# pCloud_ESP9266.net
KiCad netlist of a schematic drawn in EAGLE
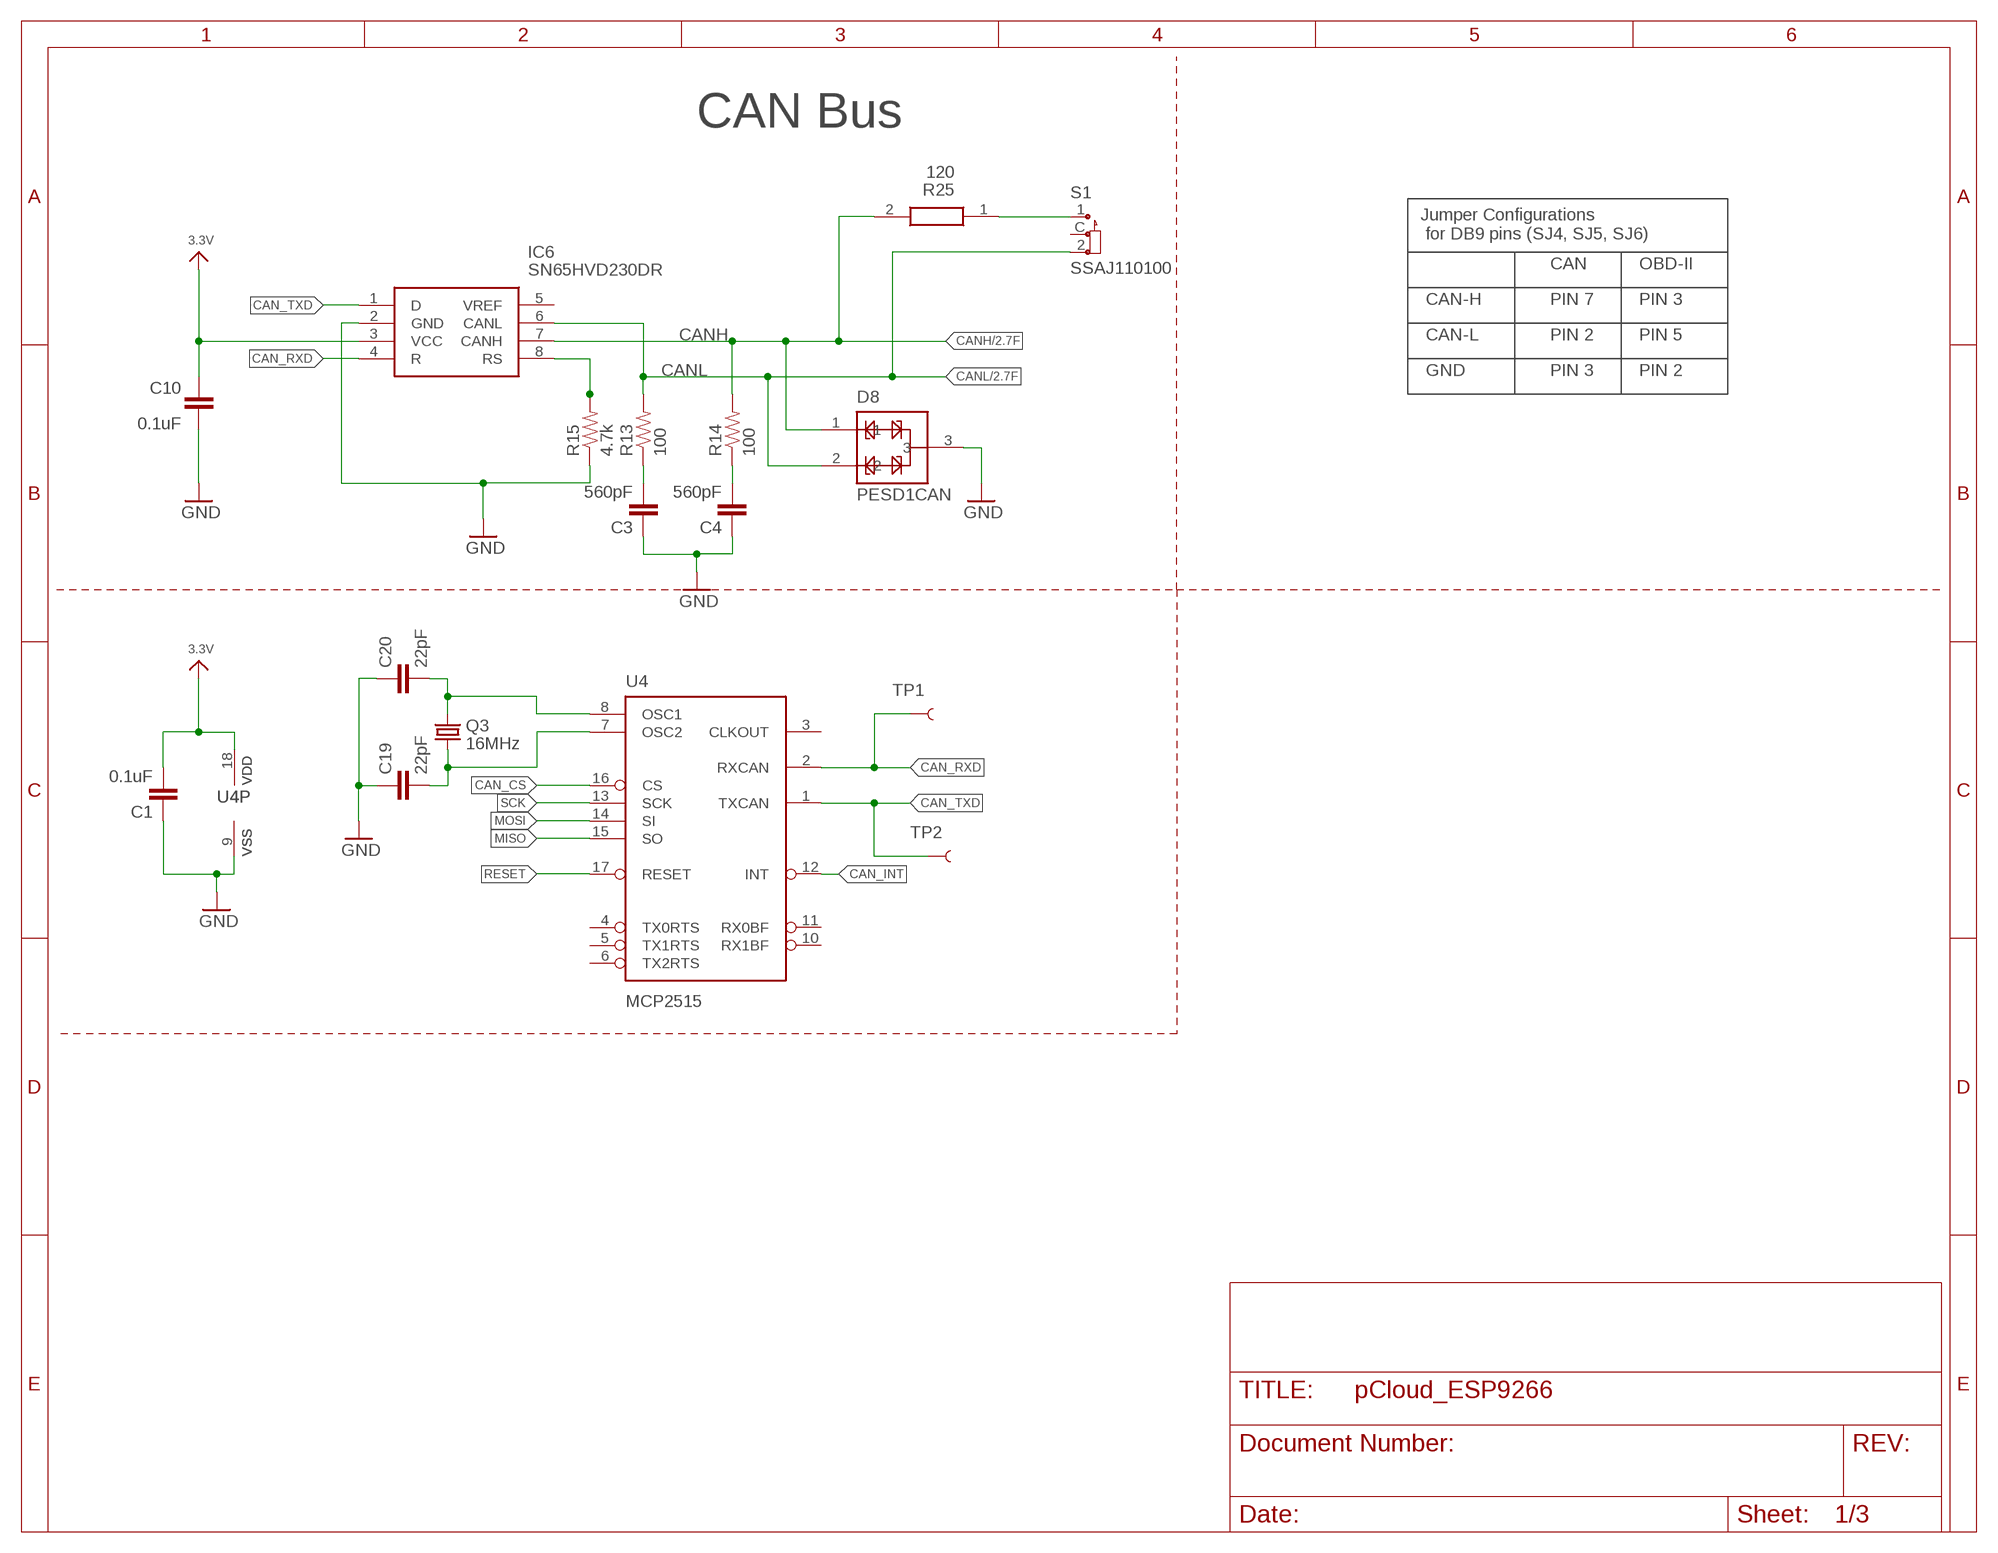
[diagram p0: schematic, sheet 1]
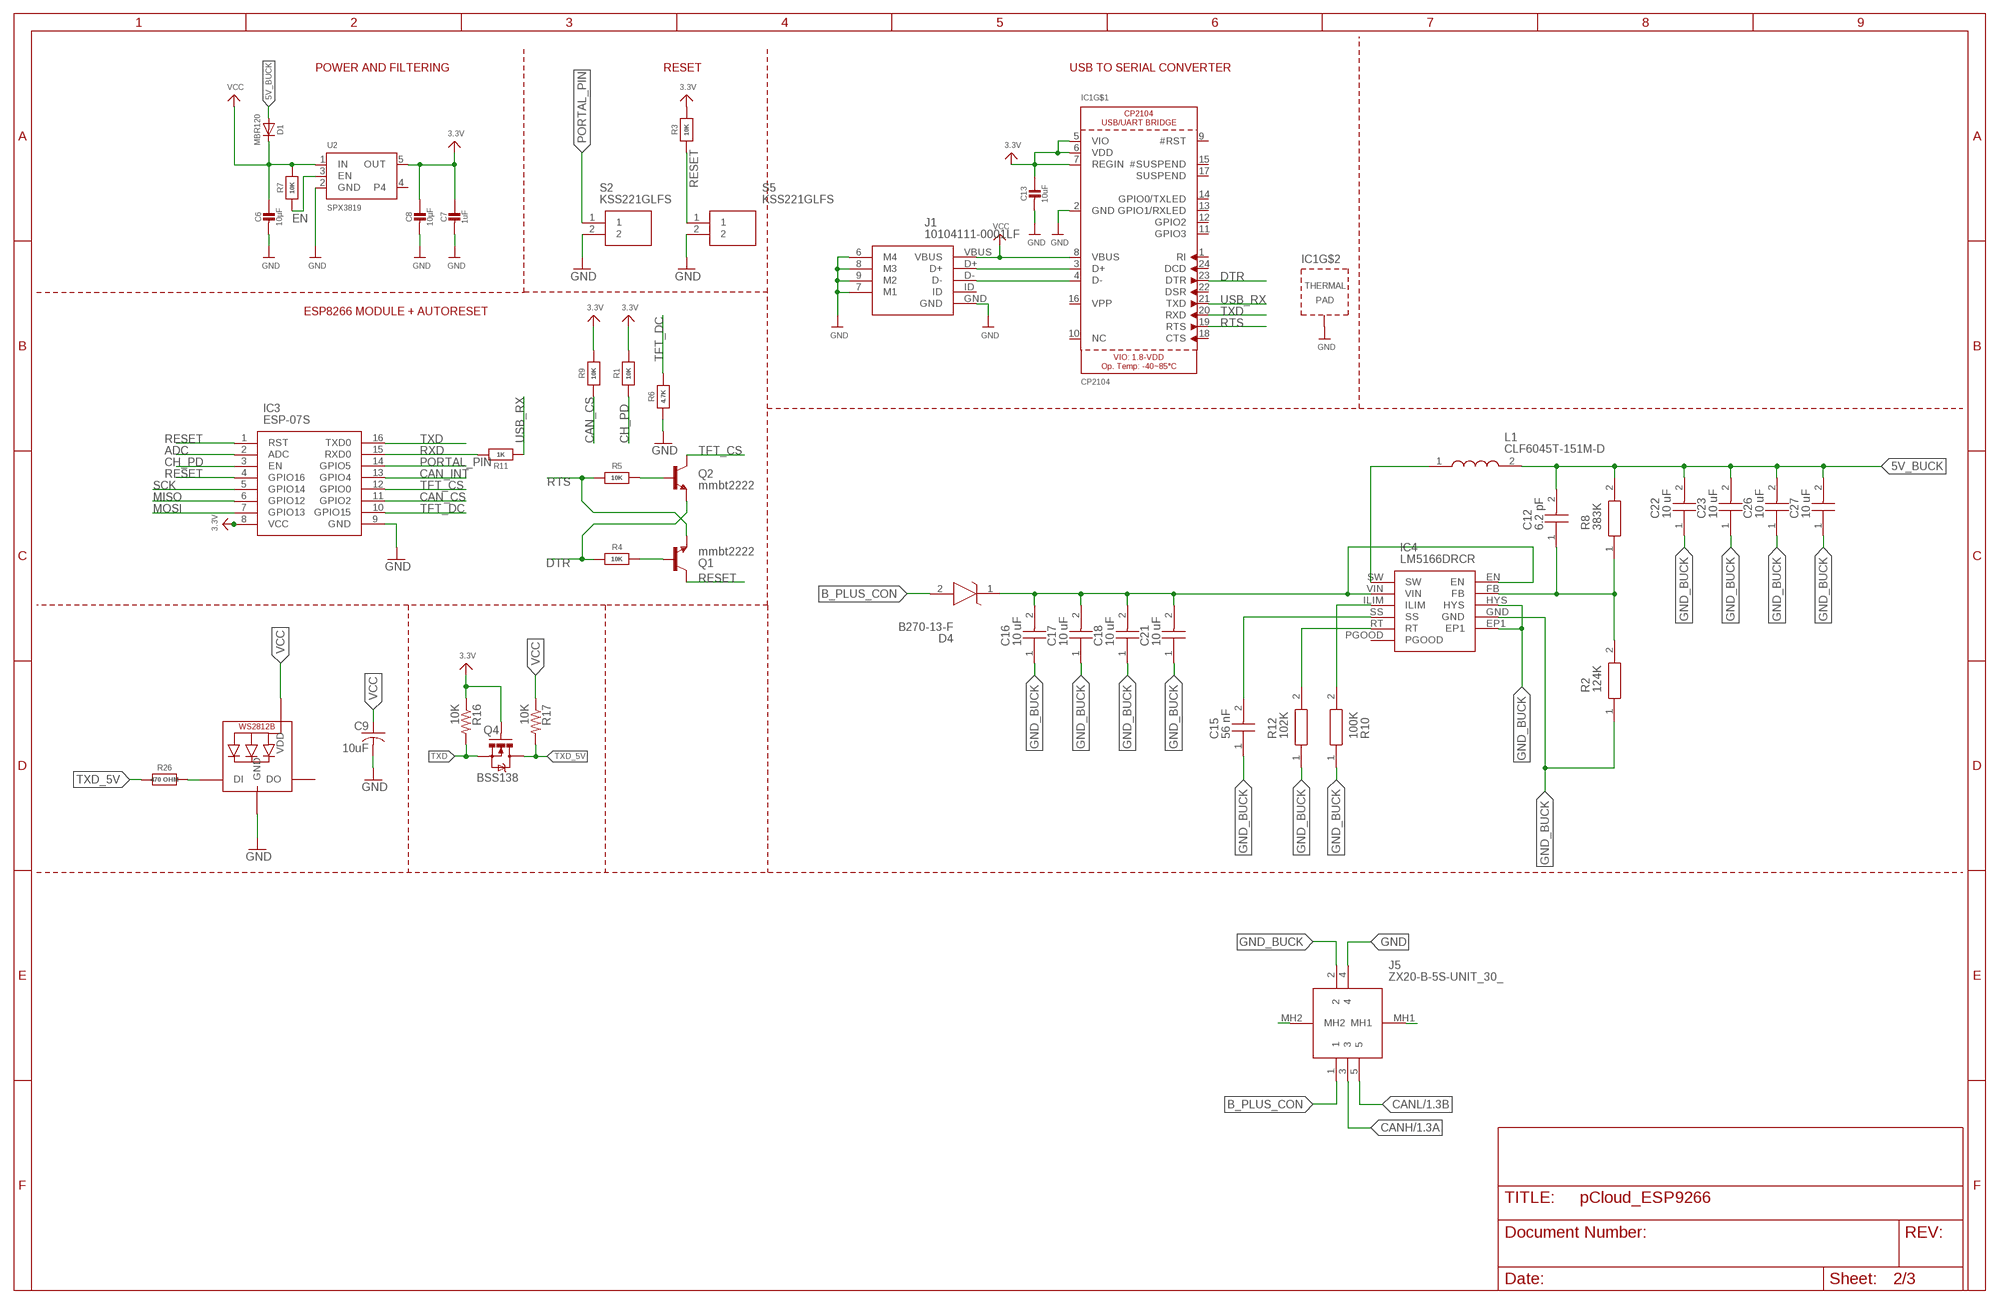
[diagram p1: schematic, sheet 2]
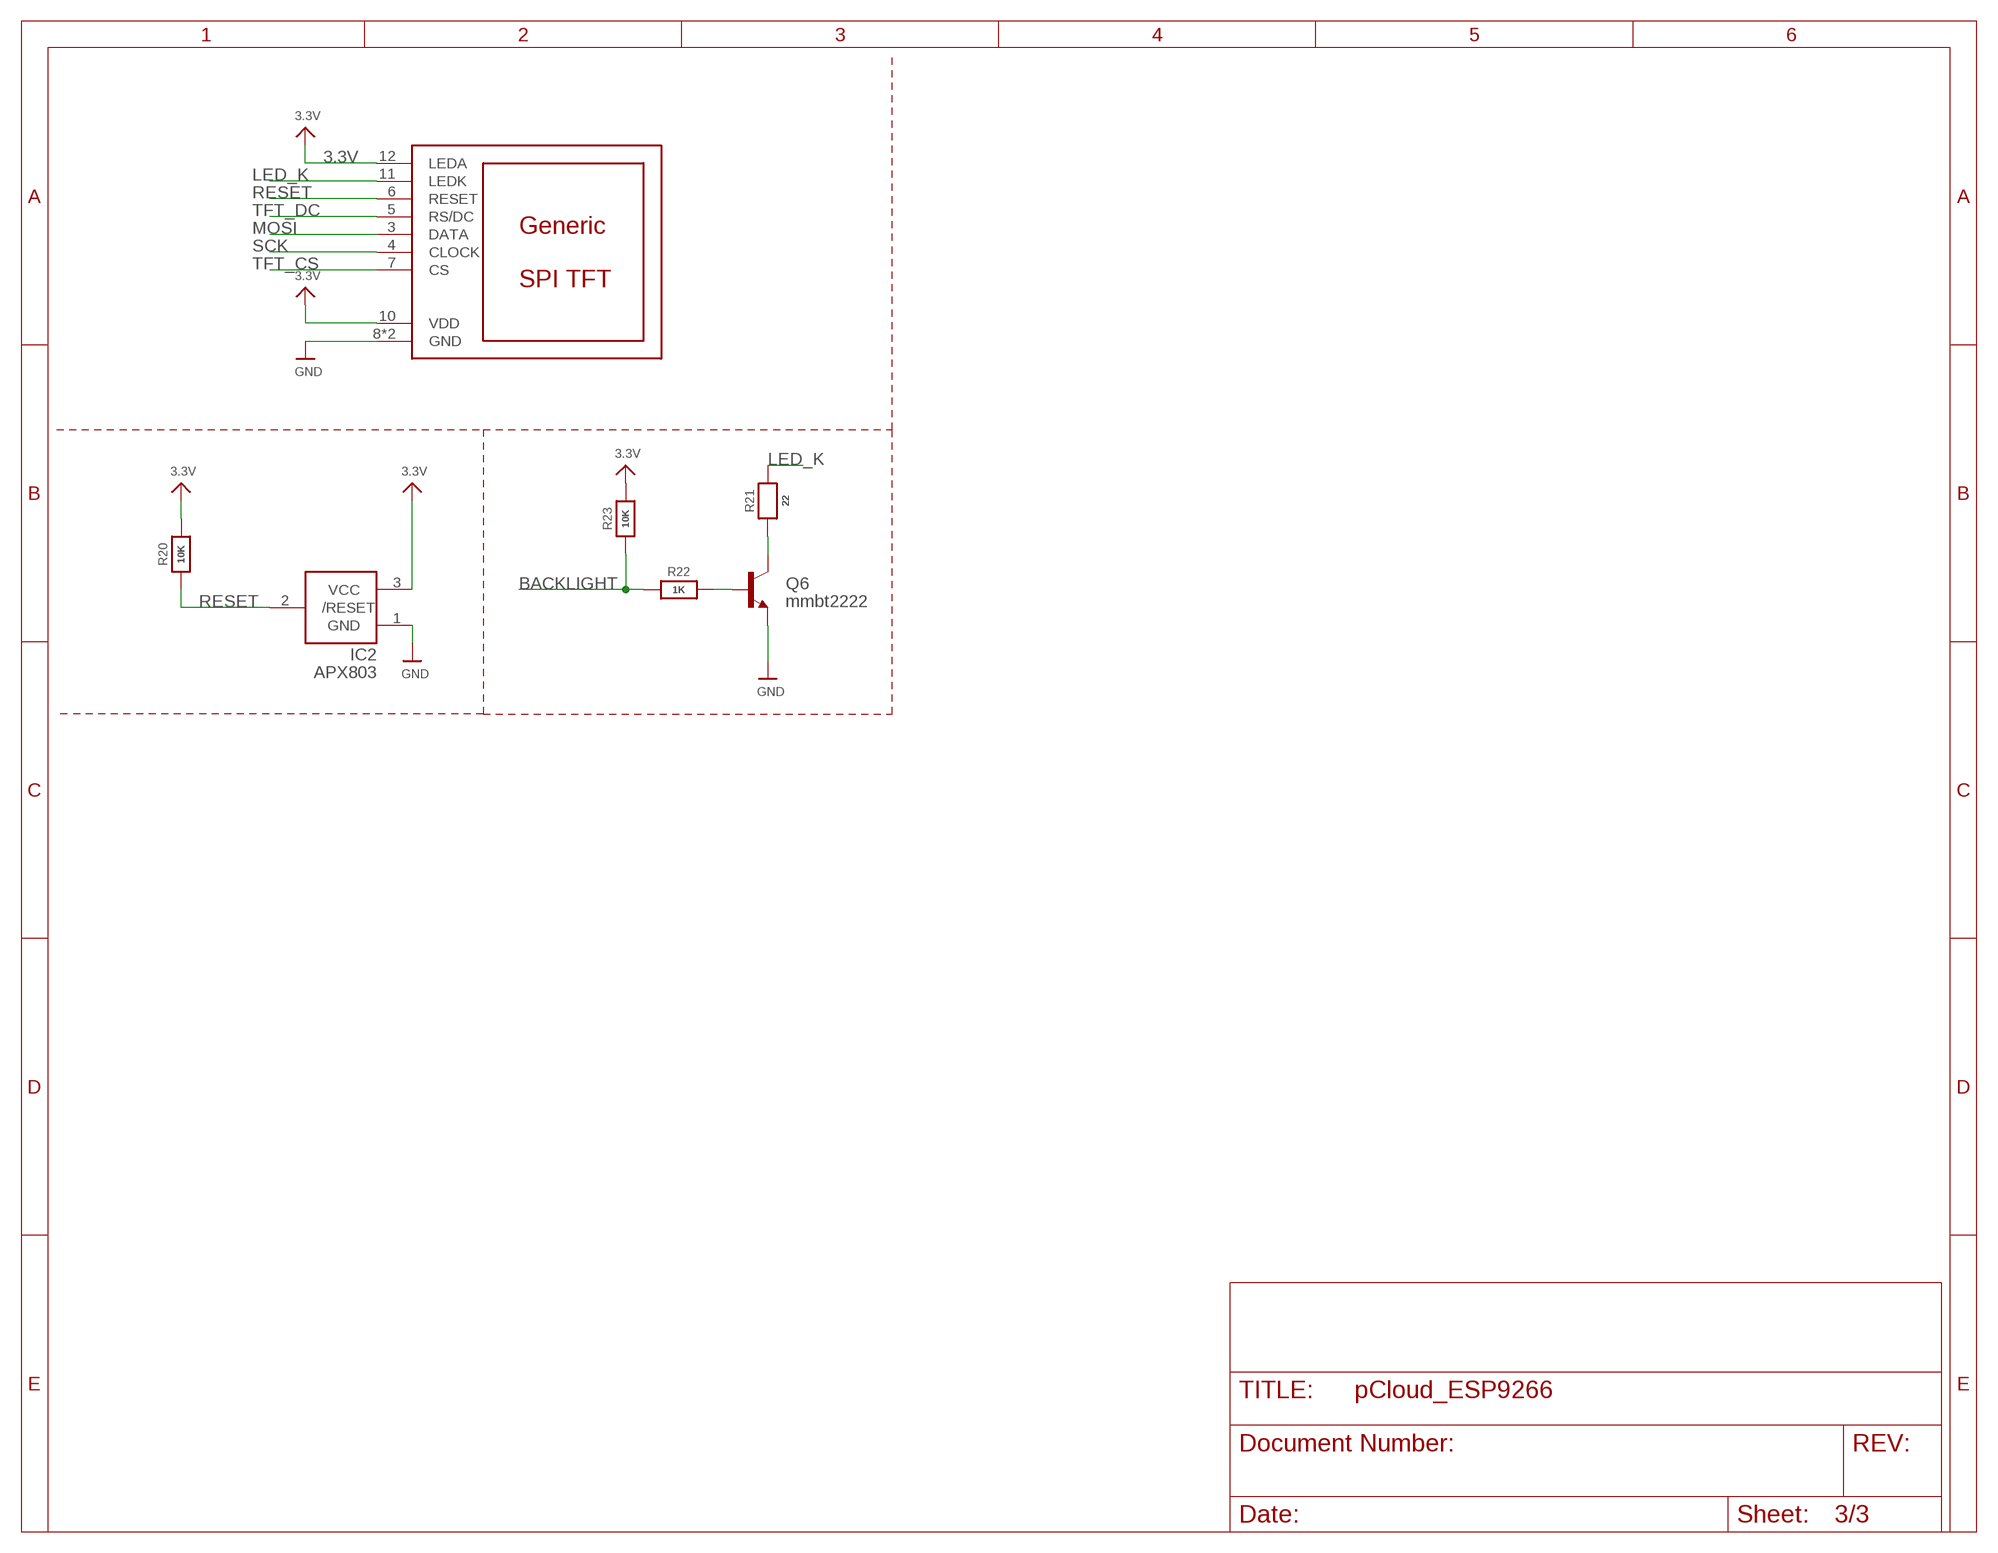
[diagram p2: schematic, sheet 3]

(export (version "E")
  (design (tool "Eeschema 10.0.6"))
  (components
    (comp (ref "C6")
      (value "10µF")
      (footprint "eagle-import:0805")
      (libsource (lib "eagle-import") (part "CAP_CERAMIC0805"))
    )
    (comp (ref "C7")
      (value "1uF")
      (footprint "eagle-import:0603")
      (libsource (lib "eagle-import") (part "CAP_CERAMIC0603"))
    )
    (comp (ref "C8")
      (value "10µF")
      (footprint "eagle-import:0805")
      (libsource (lib "eagle-import") (part "CAP_CERAMIC0805"))
    )
    (comp (ref "C9")
      (value "10uF")
      (footprint "eagle-import:C0805K")
      (libsource (lib "eagle-import") (part "C-USC0805K"))
    )
    (comp (ref "C12")
      (value "6.2 pF")
      (footprint "eagle-import:CAPC1005X55N")
      (fields
        (field (name "ARROW_PART_NUMBER") "GCM155R71C473KA37J")
        (field (name "MOUSER_PART_NUMBER") "81-GCM155R71C473KA7J")
      )
      (libsource (lib "eagle-import") (part "GCM155R71C473KA37J"))
    )
    (comp (ref "C13")
      (value "10uF")
      (footprint "eagle-import:0805")
      (libsource (lib "eagle-import") (part "CAP_CERAMIC0805"))
    )
    (comp (ref "C15")
      (value "56 nF")
      (footprint "eagle-import:CAPC1005X55N")
      (fields
        (field (name "ARROW_PART_NUMBER") "GCM155R71C473KA37J")
        (field (name "MOUSER_PART_NUMBER") "81-GCM155R71C473KA7J")
      )
      (libsource (lib "eagle-import") (part "GCM155R71C473KA37J"))
    )
    (comp (ref "C16")
      (value "10 uF")
      (footprint "eagle-import:CAPC3225X270N")
      (fields
        (field (name "ARROW_PART_NUMBER") "GRM32ER72A225KA35L")
        (field (name "MOUSER_PART_NUMBER") "81-GRM32ER72A225KA35")
      )
      (libsource (lib "eagle-import") (part "GRM32ER72A225KA35L"))
    )
    (comp (ref "C17")
      (value "10 uF")
      (footprint "eagle-import:CAPC3225X270N")
      (fields
        (field (name "ARROW_PART_NUMBER") "GRM32ER72A225KA35L")
        (field (name "MOUSER_PART_NUMBER") "81-GRM32ER72A225KA35")
      )
      (libsource (lib "eagle-import") (part "GRM32ER72A225KA35L"))
    )
    (comp (ref "C18")
      (value "10 uF")
      (footprint "eagle-import:CAPC3225X270N")
      (fields
        (field (name "ARROW_PART_NUMBER") "GRM32ER72A225KA35L")
        (field (name "MOUSER_PART_NUMBER") "81-GRM32ER72A225KA35")
      )
      (libsource (lib "eagle-import") (part "GRM32ER72A225KA35L"))
    )
    (comp (ref "C21")
      (value "10 uF")
      (footprint "eagle-import:CAPC3225X270N")
      (fields
        (field (name "ARROW_PART_NUMBER") "GRM32ER72A225KA35L")
        (field (name "MOUSER_PART_NUMBER") "81-GRM32ER72A225KA35")
      )
      (libsource (lib "eagle-import") (part "GRM32ER72A225KA35L"))
    )
    (comp (ref "C22")
      (value "10 uF")
      (footprint "eagle-import:CAPC3225X270N")
      (fields
        (field (name "ARROW_PART_NUMBER") "GRM32ER72A225KA35L")
        (field (name "MOUSER_PART_NUMBER") "81-GRM32ER72A225KA35")
      )
      (libsource (lib "eagle-import") (part "GRM32ER72A225KA35L"))
    )
    (comp (ref "C23")
      (value "10 uF")
      (footprint "eagle-import:CAPC3225X270N")
      (fields
        (field (name "ARROW_PART_NUMBER") "GRM32ER72A225KA35L")
        (field (name "MOUSER_PART_NUMBER") "81-GRM32ER72A225KA35")
      )
      (libsource (lib "eagle-import") (part "GRM32ER72A225KA35L"))
    )
    (comp (ref "C26")
      (value "10 uF")
      (footprint "eagle-import:CAPC3225X270N")
      (fields
        (field (name "ARROW_PART_NUMBER") "GRM32ER72A225KA35L")
        (field (name "MOUSER_PART_NUMBER") "81-GRM32ER72A225KA35")
      )
      (libsource (lib "eagle-import") (part "GRM32ER72A225KA35L"))
    )
    (comp (ref "C27")
      (value "10 uF")
      (footprint "eagle-import:CAPC3225X270N")
      (fields
        (field (name "ARROW_PART_NUMBER") "GRM32ER72A225KA35L")
        (field (name "MOUSER_PART_NUMBER") "81-GRM32ER72A225KA35")
      )
      (libsource (lib "eagle-import") (part "GRM32ER72A225KA35L"))
    )
    (comp (ref "D1")
      (value "MBR120")
      (footprint "eagle-import:SOD-123")
      (libsource (lib "eagle-import") (part "DIODESOD-123"))
    )
    (comp (ref "D4")
      (value "B270-13-F")
      (footprint "eagle-import:DIOM5336X250N")
      (fields (field (name "ARROW_PART_NUMBER") "B170B-13-F"))
      (libsource (lib "eagle-import") (part "B270B-13-F"))
    )
    (comp (ref "IC1")
      (value "CP2104")
      (footprint "eagle-import:QFN24_4MM_SMSC")
      (libsource (lib "eagle-import") (part "CP2104"))
    )
    (comp (ref "IC3")
      (value "ESP-07S")
      (footprint "eagle-import:ESP07S")
      (fields (field (name "MOUSER_PART_NUMBER") "223-ESP-07S") (field (name "RS_PART_NUMBER") "1372785"))
      (libsource (lib "eagle-import") (part "ESP-07S"))
    )
    (comp (ref "IC4")
      (value "LM5166DRCR")
      (footprint "eagle-import:TPS74901DRCR")
      (fields (field (name "MOUSER_PART_NUMBER") "595-LM5166DRCR"))
      (libsource (lib "eagle-import") (part "LM5166DRCR"))
    )
    (comp (ref "J1")
      (value "10104111-0001LF")
      (footprint "eagle-import:101041110001LF")
      (fields (field (name "MOUSER_PART_NUMBER") "649-10104111-0001LF"))
      (libsource (lib "eagle-import") (part "10104111-0001LF"))
    )
    (comp (ref "J5")
      (value "ZX20-B-5S-UNIT_30_")
      (footprint "eagle-import:ZX20B5SUNIT30")
      (fields
        (field (name "ARROW_PART_NUMBER") "ZX20-B-5S-UNIT(30)")
        (field (name "MOUSER_PART_NUMBER") "798-ZX20-B-5S-UNIT30")
      )
      (libsource (lib "eagle-import") (part "ZX20-B-5S-UNIT_30_"))
    )
    (comp (ref "L1")
      (value "CLF6045T-151M-D")
      (footprint "eagle-import:CLF6045T151MD")
      (fields (field (name "MOUSER_PART_NUMBER") "810-CLF6045T-151M-D"))
      (libsource (lib "eagle-import") (part "CLF6045T-151M-D"))
    )
    (comp (ref "LED4")
      (value "WS2812B5050")
      (footprint "eagle-import:WS2812B")
      (libsource (lib "eagle-import") (part "WS2812B5050"))
    )
    (comp (ref "Q1")
      (value "mmbt2222")
      (footprint "eagle-import:SOT23-3")
      (libsource (lib "eagle-import") (part "TRANSISTOR_NPNSOT23-3"))
    )
    (comp (ref "Q2")
      (value "mmbt2222")
      (footprint "eagle-import:SOT23-3")
      (libsource (lib "eagle-import") (part "TRANSISTOR_NPNSOT23-3"))
    )
    (comp (ref "Q4")
      (value "BSS138")
      (footprint "eagle-import:SOT23-3")
      (libsource (lib "eagle-import") (part "MOSFET-NCHANNELSMD"))
    )
    (comp (ref "R1")
      (value "10K")
      (footprint "eagle-import:0603")
      (libsource (lib "eagle-import") (part "RESISTOR0603"))
    )
    (comp (ref "R2")
      (value "124K")
      (footprint "eagle-import:RESC1005X40N")
      (fields
        (field (name "ARROW_PART_NUMBER") "RC0402FR-07100KP")
        (field (name "MOUSER_PART_NUMBER") "603-RC0402FR-07100KP")
      )
      (libsource (lib "eagle-import") (part "RC0402FR-07100KP"))
    )
    (comp (ref "R3")
      (value "10K")
      (footprint "eagle-import:0603")
      (libsource (lib "eagle-import") (part "RESISTOR0603"))
    )
    (comp (ref "R4")
      (value "10K")
      (footprint "eagle-import:0603")
      (libsource (lib "eagle-import") (part "RESISTOR0603"))
    )
    (comp (ref "R5")
      (value "10K")
      (footprint "eagle-import:0603")
      (libsource (lib "eagle-import") (part "RESISTOR_0603MP"))
    )
    (comp (ref "R6")
      (value "4.7K")
      (footprint "eagle-import:0603")
      (libsource (lib "eagle-import") (part "RESISTOR0603"))
    )
    (comp (ref "R7")
      (value "10K")
      (footprint "eagle-import:0603")
      (libsource (lib "eagle-import") (part "RESISTOR0603"))
    )
    (comp (ref "R8")
      (value "383K")
      (footprint "eagle-import:RESC1005X40N")
      (fields
        (field (name "ARROW_PART_NUMBER") "RC0402FR-07100KP")
        (field (name "MOUSER_PART_NUMBER") "603-RC0402FR-07100KP")
      )
      (libsource (lib "eagle-import") (part "RC0402FR-07100KP"))
    )
    (comp (ref "R9")
      (value "10K")
      (footprint "eagle-import:0603")
      (libsource (lib "eagle-import") (part "RESISTOR0603"))
    )
    (comp (ref "R10")
      (value "100K")
      (footprint "eagle-import:RESC1005X40N")
      (fields
        (field (name "ARROW_PART_NUMBER") "RC0402FR-07100KP")
        (field (name "MOUSER_PART_NUMBER") "603-RC0402FR-07100KP")
      )
      (libsource (lib "eagle-import") (part "RC0402FR-07100KP"))
    )
    (comp (ref "R11")
      (value "1K")
      (footprint "eagle-import:0603")
      (libsource (lib "eagle-import") (part "RESISTOR_0603MP"))
    )
    (comp (ref "R12")
      (value "102K")
      (footprint "eagle-import:RESC1005X40N")
      (fields
        (field (name "ARROW_PART_NUMBER") "RC0402FR-07100KP")
        (field (name "MOUSER_PART_NUMBER") "603-RC0402FR-07100KP")
      )
      (libsource (lib "eagle-import") (part "RC0402FR-07100KP"))
    )
    (comp (ref "R16")
      (value "10K")
      (footprint "eagle-import:0603")
      (libsource (lib "eagle-import") (part "RESISTOR0603-RES"))
    )
    (comp (ref "R17")
      (value "10K")
      (footprint "eagle-import:0603")
      (libsource (lib "eagle-import") (part "RESISTOR0603-RES"))
    )
    (comp (ref "R26")
      (value "470 OHM")
      (footprint "eagle-import:_0805MP")
      (libsource (lib "eagle-import") (part "RESISTOR_0805MP"))
    )
    (comp (ref "S2")
      (value "KSS221GLFS")
      (footprint "eagle-import:KSS")
      (fields (field (name "MOUSER_PART_NUMBER") "611-KSS221GLFS"))
      (libsource (lib "eagle-import") (part "KSS221GLFS"))
    )
    (comp (ref "S5")
      (value "KSS221GLFS")
      (footprint "eagle-import:KSS")
      (fields (field (name "MOUSER_PART_NUMBER") "611-KSS221GLFS"))
      (libsource (lib "eagle-import") (part "KSS221GLFS"))
    )
    (comp (ref "U2")
      (value "SPX3819")
      (footprint "eagle-import:SOT23-5")
      (libsource (lib "eagle-import") (part "VREG_SOT23-5"))
    )
    (comp (ref "DISP1")
      (value "DISP_LCD_GENERIC_SPI_1.14IN_240X135_WRAPUNDER")
      (footprint "eagle-import:TFT_1.14IN_240X135_WRAPUNDER")
      (libsource (lib "eagle-import") (part "DISP_LCD_GENERIC_SPI_1.14IN_240X135_WRAPUNDER"))
    )
    (comp (ref "IC2")
      (value "APX803")
      (footprint "eagle-import:SOT23")
      (libsource (lib "eagle-import") (part "AXP083-SAG"))
    )
    (comp (ref "Q6")
      (value "mmbt2222")
      (footprint "eagle-import:SOT23-3")
      (libsource (lib "eagle-import") (part "TRANSISTOR_NPNSOT23-3"))
    )
    (comp (ref "R20")
      (value "10K")
      (footprint "eagle-import:0603")
      (libsource (lib "eagle-import") (part "RESISTOR0603"))
    )
    (comp (ref "R21")
      (value "22")
      (footprint "eagle-import:0603")
      (libsource (lib "eagle-import") (part "RESISTOR0603"))
    )
    (comp (ref "R22")
      (value "1K")
      (footprint "eagle-import:0603")
      (libsource (lib "eagle-import") (part "RESISTOR0603"))
    )
    (comp (ref "R23")
      (value "10K")
      (footprint "eagle-import:0603")
      (libsource (lib "eagle-import") (part "RESISTOR0603"))
    )
    (comp (ref "C1")
      (value "0.1uF")
      (footprint "eagle-import:0603")
      (libsource (lib "eagle-import") (part "0.1UF-0603-25V-(+80/-20%)"))
    )
    (comp (ref "C3")
      (value "560pF")
      (footprint "eagle-import:0603")
      (libsource (lib "eagle-import") (part "560PF-0603-50V-5%"))
    )
    (comp (ref "C4")
      (value "560pF")
      (footprint "eagle-import:0603")
      (libsource (lib "eagle-import") (part "560PF-0603-50V-5%"))
    )
    (comp (ref "C10")
      (value "0.1uF")
      (footprint "eagle-import:0603")
      (libsource (lib "eagle-import") (part "0.1UF-0603-25V-(+80/-20%)"))
    )
    (comp (ref "C19")
      (value "22pF")
      (footprint "eagle-import:0603")
      (libsource (lib "eagle-import") (part "22PF-0603-50V-5%"))
    )
    (comp (ref "C20")
      (value "22pF")
      (footprint "eagle-import:0603")
      (libsource (lib "eagle-import") (part "22PF-0603-50V-5%"))
    )
    (comp (ref "D8")
      (value "PESD1CAN")
      (footprint "eagle-import:SOT23-3")
      (libsource (lib "eagle-import") (part "PESD1CAN"))
    )
    (comp (ref "IC6")
      (value "SN65HVD230DR")
      (footprint "eagle-import:SOT127P600X175-8N")
      (fields (field (name "MOUSER_PART_NUMBER") "595-SN65HVD230DR"))
      (libsource (lib "eagle-import") (part "SN65HVD230DR"))
    )
    (comp (ref "Q3")
      (value "16MHz")
      (footprint "eagle-import:CRYSTAL-SMD-5X3")
      (libsource (lib "eagle-import") (part "CRYSTAL5X3"))
    )
    (comp (ref "R13")
      (value "100")
      (footprint "eagle-import:0603")
      (libsource (lib "eagle-import") (part "100OHM-0603-1/10W-1%"))
    )
    (comp (ref "R14")
      (value "100")
      (footprint "eagle-import:0603")
      (libsource (lib "eagle-import") (part "100OHM-0603-1/10W-1%"))
    )
    (comp (ref "R15")
      (value "4.7k")
      (footprint "eagle-import:0603")
      (libsource (lib "eagle-import") (part "4.7KOHM-0603-1/10W-1%"))
    )
    (comp (ref "R25")
      (value "120")
      (footprint "eagle-import:RESC1608X55N")
      (fields
        (field (name "ARROW_PART_NUMBER") "RC0603JR-7W120RL")
        (field (name "MOUSER_PART_NUMBER") "603-RC0603JR-7W120RL")
      )
      (libsource (lib "eagle-import") (part "RC0603JR-7W120RL"))
    )
    (comp (ref "S1")
      (value "SSAJ110100")
      (footprint "eagle-import:SW_SSAJ110100")
      (fields (field (name "MF") "ALPS"))
      (libsource (lib "eagle-import") (part "SSAJ110100"))
    )
    (comp (ref "TP1")
      (value "TEST-POINT3X5")
      (footprint "eagle-import:PAD.03X.05")
      (libsource (lib "eagle-import") (part "TEST-POINT3X5"))
    )
    (comp (ref "TP2")
      (value "TEST-POINT3X5")
      (footprint "eagle-import:PAD.03X.05")
      (libsource (lib "eagle-import") (part "TEST-POINT3X5"))
    )
    (comp (ref "U4")
      (value "MCP2515")
      (footprint "eagle-import:SO-18W")
      (libsource (lib "eagle-import") (part "MCP2510SO"))
    )
  )
  (nets
    (net (code "1") (name "3.3V") (class "Default")
      (node (ref "C1") (pin "2") (pinfunction "2_2") (pintype "passive"))
      (node (ref "C10") (pin "2") (pinfunction "2_2") (pintype "passive"))
      (node (ref "C13") (pin "1") (pinfunction "P$1_1") (pintype "passive"))
      (node (ref "C7") (pin "1") (pinfunction "P$1_1") (pintype "passive"))
      (node (ref "C8") (pin "1") (pinfunction "P$1_1") (pintype "passive"))
      (node (ref "DISP1") (pin "10") (pinfunction "VDD_10") (pintype "power_in"))
      (node (ref "DISP1") (pin "12") (pinfunction "LEDA_12") (pintype "input"))
      (node (ref "IC1") (pin "5") (pinfunction "VIO_5") (pintype "power_in"))
      (node (ref "IC1") (pin "6") (pinfunction "VDD_6") (pintype "power_in"))
      (node (ref "IC1") (pin "7") (pinfunction "REGIN_7") (pintype "power_in"))
      (node (ref "IC2") (pin "3") (pinfunction "VCC_3") (pintype "power_in"))
      (node (ref "IC3") (pin "8") (pinfunction "VCC_8") (pintype "bidirectional"))
      (node (ref "IC6") (pin "3") (pinfunction "VCC_3") (pintype "bidirectional"))
      (node (ref "Q4") (pin "1") (pinfunction "G_1") (pintype "passive"))
      (node (ref "R1") (pin "2") (pinfunction "2_2") (pintype "passive"))
      (node (ref "R16") (pin "1") (pinfunction "1_1") (pintype "passive"))
      (node (ref "R20") (pin "2") (pinfunction "2_2") (pintype "passive"))
      (node (ref "R23") (pin "2") (pinfunction "2_2") (pintype "passive"))
      (node (ref "R3") (pin "2") (pinfunction "2_2") (pintype "passive"))
      (node (ref "R9") (pin "2") (pinfunction "2_2") (pintype "passive"))
      (node (ref "U2") (pin "5") (pinfunction "OUT_5") (pintype "bidirectional"))
      (node (ref "U4") (pin "18") (pinfunction "VDD_18") (pintype "power_in"))
    )
    (net (code "2") (name "5V_BUCK") (class "Default")
      (node (ref "C12") (pin "2") (pinfunction "2_2") (pintype "bidirectional"))
      (node (ref "C22") (pin "2") (pinfunction "C2_2") (pintype "bidirectional"))
      (node (ref "C23") (pin "2") (pinfunction "C2_2") (pintype "bidirectional"))
      (node (ref "C26") (pin "2") (pinfunction "C2_2") (pintype "bidirectional"))
      (node (ref "C27") (pin "2") (pinfunction "C2_2") (pintype "bidirectional"))
      (node (ref "D1") (pin "A") (pinfunction "A_A") (pintype "passive"))
      (node (ref "L1") (pin "2") (pinfunction "2_2") (pintype "bidirectional"))
      (node (ref "R8") (pin "2") (pinfunction "2_2") (pintype "bidirectional"))
    )
    (net (code "3") (name "ADC") (class "Default")
      (node (ref "IC3") (pin "2") (pinfunction "ADC_2") (pintype "bidirectional"))
    )
    (net (code "4") (name "BACKLIGHT") (class "Default")
      (node (ref "R22") (pin "1") (pinfunction "1_1") (pintype "passive"))
      (node (ref "R23") (pin "1") (pinfunction "1_1") (pintype "passive"))
    )
    (net (code "5") (name "B_PLUS_CON") (class "Default")
      (node (ref "D4") (pin "2") (pinfunction "A_2") (pintype "bidirectional"))
      (node (ref "J5") (pin "1") (pinfunction "1_1") (pintype "bidirectional"))
    )
    (net (code "6") (name "CANH") (class "Default")
      (node (ref "D8") (pin "1") (pinfunction "1_1") (pintype "bidirectional"))
      (node (ref "IC6") (pin "7") (pinfunction "CANH_7") (pintype "bidirectional"))
      (node (ref "J5") (pin "3") (pinfunction "3_3") (pintype "bidirectional"))
      (node (ref "R14") (pin "2") (pinfunction "2_2") (pintype "passive"))
      (node (ref "R25") (pin "2") (pinfunction "2_2") (pintype "bidirectional"))
    )
    (net (code "7") (name "CANL") (class "Default")
      (node (ref "D8") (pin "2") (pinfunction "2_2") (pintype "bidirectional"))
      (node (ref "IC6") (pin "6") (pinfunction "CANL_6") (pintype "bidirectional"))
      (node (ref "J5") (pin "5") (pinfunction "5_5") (pintype "bidirectional"))
      (node (ref "R13") (pin "2") (pinfunction "2_2") (pintype "passive"))
      (node (ref "S1") (pin "2") (pinfunction "2_2") (pintype "passive"))
    )
    (net (code "8") (name "CAN_CS") (class "Default")
      (node (ref "IC3") (pin "11") (pinfunction "GPIO2_11") (pintype "bidirectional"))
      (node (ref "R9") (pin "1") (pinfunction "1_1") (pintype "passive"))
      (node (ref "U4") (pin "16") (pinfunction "CS_16") (pintype "input"))
    )
    (net (code "9") (name "CAN_INT") (class "Default")
      (node (ref "IC3") (pin "13") (pinfunction "GPIO4_13") (pintype "bidirectional"))
      (node (ref "U4") (pin "12") (pinfunction "INT_12") (pintype "output"))
    )
    (net (code "10") (name "CAN_RXD") (class "Default")
      (node (ref "IC6") (pin "4") (pinfunction "R_4") (pintype "bidirectional"))
      (node (ref "TP1") (pin "P$1") (pinfunction "1_P$1") (pintype "bidirectional"))
      (node (ref "U4") (pin "2") (pinfunction "RXCAN_2") (pintype "input"))
    )
    (net (code "11") (name "CAN_TXD") (class "Default")
      (node (ref "IC6") (pin "1") (pinfunction "D_1") (pintype "bidirectional"))
      (node (ref "TP2") (pin "P$1") (pinfunction "1_P$1") (pintype "bidirectional"))
      (node (ref "U4") (pin "1") (pinfunction "TXCAN_1") (pintype "output"))
    )
    (net (code "12") (name "CH_PD") (class "Default")
      (node (ref "IC3") (pin "3") (pinfunction "EN_3") (pintype "bidirectional"))
      (node (ref "R1") (pin "1") (pinfunction "1_1") (pintype "passive"))
    )
    (net (code "13") (name "DTR") (class "Default")
      (node (ref "IC1") (pin "23") (pinfunction "DTR_23") (pintype "output"))
      (node (ref "Q2") (pin "2") (pinfunction "E_2") (pintype "passive"))
      (node (ref "R4") (pin "1") (pinfunction "1_1") (pintype "passive"))
    )
    (net (code "14") (name "EN") (class "Default")
      (node (ref "R7") (pin "1") (pinfunction "1_1") (pintype "passive"))
      (node (ref "U2") (pin "3") (pinfunction "EN_3") (pintype "bidirectional"))
    )
    (net (code "15") (name "GND") (class "Default")
      (node (ref "C1") (pin "1") (pinfunction "1_1") (pintype "passive"))
      (node (ref "C10") (pin "1") (pinfunction "1_1") (pintype "passive"))
      (node (ref "C13") (pin "2") (pinfunction "P$2_2") (pintype "passive"))
      (node (ref "C19") (pin "1") (pinfunction "1_1") (pintype "passive"))
      (node (ref "C20") (pin "1") (pinfunction "1_1") (pintype "passive"))
      (node (ref "C3") (pin "1") (pinfunction "1_1") (pintype "passive"))
      (node (ref "C4") (pin "1") (pinfunction "1_1") (pintype "passive"))
      (node (ref "C6") (pin "2") (pinfunction "P$2_2") (pintype "passive"))
      (node (ref "C7") (pin "2") (pinfunction "P$2_2") (pintype "passive"))
      (node (ref "C8") (pin "2") (pinfunction "P$2_2") (pintype "passive"))
      (node (ref "C9") (pin "2") (pinfunction "2_2") (pintype "passive"))
      (node (ref "D8") (pin "3") (pinfunction "3_3") (pintype "bidirectional"))
      (node (ref "DISP1") (pin "13") (pinfunction "GND_13") (pintype "power_in"))
      (node (ref "DISP1") (pin "8") (pinfunction "GND_8") (pintype "power_in"))
      (node (ref "IC1") (pin "2") (pinfunction "GND_2") (pintype "power_in"))
      (node (ref "IC1") (pin "THERM") (pinfunction "TP_THERM") (pintype "power_in"))
      (node (ref "IC2") (pin "1") (pinfunction "GND_1") (pintype "power_in"))
      (node (ref "IC3") (pin "9") (pinfunction "GND_9") (pintype "bidirectional"))
      (node (ref "IC6") (pin "2") (pinfunction "GND_2") (pintype "bidirectional"))
      (node (ref "J1") (pin "6") (pinfunction "M4_6") (pintype "bidirectional"))
      (node (ref "J1") (pin "7") (pinfunction "M1_7") (pintype "bidirectional"))
      (node (ref "J1") (pin "8") (pinfunction "M3_8") (pintype "bidirectional"))
      (node (ref "J1") (pin "9") (pinfunction "M2_9") (pintype "bidirectional"))
      (node (ref "J1") (pin "GND") (pinfunction "GND_GND") (pintype "bidirectional"))
      (node (ref "J5") (pin "4") (pinfunction "4_4") (pintype "bidirectional"))
      (node (ref "LED4") (pin "3-GND") (pinfunction "GND_3-GND") (pintype "power_in"))
      (node (ref "Q6") (pin "2") (pinfunction "E_2") (pintype "passive"))
      (node (ref "R15") (pin "1") (pinfunction "1_1") (pintype "passive"))
      (node (ref "R6") (pin "1") (pinfunction "1_1") (pintype "passive"))
      (node (ref "S2") (pin "2") (pinfunction "2_2") (pintype "bidirectional"))
      (node (ref "S5") (pin "2") (pinfunction "2_2") (pintype "bidirectional"))
      (node (ref "U2") (pin "2") (pinfunction "GND_2") (pintype "bidirectional"))
      (node (ref "U4") (pin "9") (pinfunction "VSS_9") (pintype "power_in"))
    )
    (net (code "16") (name "GND_BUCK") (class "Default")
      (node (ref "C15") (pin "1") (pinfunction "1_1") (pintype "bidirectional"))
      (node (ref "C16") (pin "1") (pinfunction "C1_1") (pintype "bidirectional"))
      (node (ref "C17") (pin "1") (pinfunction "C1_1") (pintype "bidirectional"))
      (node (ref "C18") (pin "1") (pinfunction "C1_1") (pintype "bidirectional"))
      (node (ref "C21") (pin "1") (pinfunction "C1_1") (pintype "bidirectional"))
      (node (ref "C22") (pin "1") (pinfunction "C1_1") (pintype "bidirectional"))
      (node (ref "C23") (pin "1") (pinfunction "C1_1") (pintype "bidirectional"))
      (node (ref "C26") (pin "1") (pinfunction "C1_1") (pintype "bidirectional"))
      (node (ref "C27") (pin "1") (pinfunction "C1_1") (pintype "bidirectional"))
      (node (ref "IC4") (pin "EP1") (pinfunction "EP1_EP1") (pintype "bidirectional"))
      (node (ref "IC4") (pin "GND") (pinfunction "GND_GND") (pintype "bidirectional"))
      (node (ref "IC4") (pin "HYS") (pinfunction "HYS_HYS") (pintype "bidirectional"))
      (node (ref "J5") (pin "2") (pinfunction "2_2") (pintype "bidirectional"))
      (node (ref "R10") (pin "1") (pinfunction "1_1") (pintype "bidirectional"))
      (node (ref "R12") (pin "1") (pinfunction "1_1") (pintype "bidirectional"))
      (node (ref "R2") (pin "1") (pinfunction "1_1") (pintype "bidirectional"))
    )
    (net (code "17") (name "LED_K") (class "Default")
      (node (ref "DISP1") (pin "11") (pinfunction "LEDK_11") (pintype "input"))
      (node (ref "R21") (pin "2") (pinfunction "2_2") (pintype "passive"))
    )
    (net (code "18") (name "MISO") (class "Default")
      (node (ref "IC3") (pin "6") (pinfunction "GPIO12_6") (pintype "bidirectional"))
      (node (ref "U4") (pin "15") (pinfunction "SO_15") (pintype "output"))
    )
    (net (code "19") (name "MOSI") (class "Default")
      (node (ref "DISP1") (pin "3") (pinfunction "DATA_3") (pintype "bidirectional"))
      (node (ref "IC3") (pin "7") (pinfunction "GPIO13_7") (pintype "bidirectional"))
      (node (ref "U4") (pin "14") (pinfunction "SI_14") (pintype "input"))
    )
    (net (code "20") (name "Net-(C3-Pad2)") (class "Default")
      (node (ref "C3") (pin "2") (pinfunction "2_2") (pintype "passive"))
      (node (ref "R13") (pin "1") (pinfunction "1_1") (pintype "passive"))
    )
    (net (code "21") (name "Net-(C4-Pad2)") (class "Default")
      (node (ref "C4") (pin "2") (pinfunction "2_2") (pintype "passive"))
      (node (ref "R14") (pin "1") (pinfunction "1_1") (pintype "passive"))
    )
    (net (code "22") (name "Net-(C12-Pad1)") (class "Default")
      (node (ref "C12") (pin "1") (pinfunction "1_1") (pintype "bidirectional"))
      (node (ref "IC4") (pin "FB") (pinfunction "FB_FB") (pintype "bidirectional"))
      (node (ref "R2") (pin "2") (pinfunction "2_2") (pintype "bidirectional"))
      (node (ref "R8") (pin "1") (pinfunction "1_1") (pintype "bidirectional"))
    )
    (net (code "23") (name "Net-(C15-Pad2)") (class "Default")
      (node (ref "C15") (pin "2") (pinfunction "2_2") (pintype "bidirectional"))
      (node (ref "IC4") (pin "SS") (pinfunction "SS_SS") (pintype "bidirectional"))
    )
    (net (code "24") (name "Net-(C16-C2)") (class "Default")
      (node (ref "C16") (pin "2") (pinfunction "C2_2") (pintype "bidirectional"))
      (node (ref "C17") (pin "2") (pinfunction "C2_2") (pintype "bidirectional"))
      (node (ref "C18") (pin "2") (pinfunction "C2_2") (pintype "bidirectional"))
      (node (ref "C21") (pin "2") (pinfunction "C2_2") (pintype "bidirectional"))
      (node (ref "D4") (pin "1") (pinfunction "K_1") (pintype "bidirectional"))
      (node (ref "IC4") (pin "EN") (pinfunction "EN_EN") (pintype "bidirectional"))
      (node (ref "IC4") (pin "VIN") (pinfunction "VIN_VIN") (pintype "bidirectional"))
    )
    (net (code "25") (name "Net-(IC1A-D+)") (class "Default")
      (node (ref "IC1") (pin "3") (pinfunction "D+_3") (pintype "bidirectional"))
      (node (ref "J1") (pin "D+") (pinfunction "D+_D+") (pintype "bidirectional"))
    )
    (net (code "26") (name "Net-(IC1A-D-)") (class "Default")
      (node (ref "IC1") (pin "4") (pinfunction "D-_4") (pintype "bidirectional"))
      (node (ref "J1") (pin "D-") (pinfunction "D-_D-") (pintype "bidirectional"))
    )
    (net (code "27") (name "Net-(IC4-PadILIM)") (class "Default")
      (node (ref "IC4") (pin "ILIM") (pinfunction "ILIM_ILIM") (pintype "bidirectional"))
      (node (ref "R10") (pin "2") (pinfunction "2_2") (pintype "bidirectional"))
    )
    (net (code "28") (name "Net-(IC4-PadRT)") (class "Default")
      (node (ref "IC4") (pin "RT") (pinfunction "RT_RT") (pintype "bidirectional"))
      (node (ref "R12") (pin "2") (pinfunction "2_2") (pintype "bidirectional"))
    )
    (net (code "29") (name "Net-(IC4-PadSW)") (class "Default")
      (node (ref "IC4") (pin "SW") (pinfunction "SW_SW") (pintype "bidirectional"))
      (node (ref "L1") (pin "1") (pinfunction "1_1") (pintype "bidirectional"))
    )
    (net (code "30") (name "Net-(IC6-RS)") (class "Default")
      (node (ref "IC6") (pin "8") (pinfunction "RS_8") (pintype "bidirectional"))
      (node (ref "R15") (pin "2") (pinfunction "2_2") (pintype "passive"))
    )
    (net (code "31") (name "Net-(LED4-DI)") (class "Default")
      (node (ref "LED4") (pin "4-DIN") (pinfunction "DI_4-DIN") (pintype "input"))
      (node (ref "R26") (pin "2") (pinfunction "2_2") (pintype "passive"))
    )
    (net (code "32") (name "Net-(Q1-B)") (class "Default")
      (node (ref "Q1") (pin "1") (pinfunction "B_1") (pintype "passive"))
      (node (ref "R4") (pin "2") (pinfunction "2_2") (pintype "passive"))
    )
    (net (code "33") (name "Net-(Q2-B)") (class "Default")
      (node (ref "Q2") (pin "1") (pinfunction "B_1") (pintype "passive"))
      (node (ref "R5") (pin "2") (pinfunction "2_2") (pintype "passive"))
    )
    (net (code "34") (name "Net-(Q3-2)") (class "Default")
      (node (ref "C20") (pin "2") (pinfunction "2_2") (pintype "passive"))
      (node (ref "Q3") (pin "3") (pinfunction "2_3") (pintype "passive"))
      (node (ref "U4") (pin "8") (pinfunction "OSC1_8") (pintype "input"))
    )
    (net (code "35") (name "Net-(Q6-B)") (class "Default")
      (node (ref "Q6") (pin "1") (pinfunction "B_1") (pintype "passive"))
      (node (ref "R22") (pin "2") (pinfunction "2_2") (pintype "passive"))
    )
    (net (code "36") (name "Net-(Q6-C)") (class "Default")
      (node (ref "Q6") (pin "3") (pinfunction "C_3") (pintype "passive"))
      (node (ref "R21") (pin "1") (pinfunction "1_1") (pintype "passive"))
    )
    (net (code "37") (name "Net-(R25-Pad1)") (class "Default")
      (node (ref "R25") (pin "1") (pinfunction "1_1") (pintype "bidirectional"))
      (node (ref "S1") (pin "1") (pinfunction "1_1") (pintype "passive"))
    )
    (net (code "38") (name "Net-(U4A-OSC2)") (class "Default")
      (node (ref "C19") (pin "2") (pinfunction "2_2") (pintype "passive"))
      (node (ref "Q3") (pin "1") (pinfunction "1_1") (pintype "passive"))
      (node (ref "U4") (pin "7") (pinfunction "OSC2_7") (pintype "output"))
    )
    (net (code "39") (name "PORTAL_PIN") (class "Default")
      (node (ref "IC3") (pin "14") (pinfunction "GPIO5_14") (pintype "bidirectional"))
      (node (ref "S2") (pin "1") (pinfunction "1_1") (pintype "bidirectional"))
    )
    (net (code "40") (name "RESET") (class "Default")
      (node (ref "DISP1") (pin "6") (pinfunction "RESET_6") (pintype "input"))
      (node (ref "IC2") (pin "2") (pinfunction "/RESET_2") (pintype "output"))
      (node (ref "IC3") (pin "1") (pinfunction "RST_1") (pintype "bidirectional"))
      (node (ref "IC3") (pin "4") (pinfunction "GPIO16_4") (pintype "bidirectional"))
      (node (ref "Q1") (pin "3") (pinfunction "C_3") (pintype "passive"))
      (node (ref "R20") (pin "1") (pinfunction "1_1") (pintype "passive"))
      (node (ref "R3") (pin "1") (pinfunction "1_1") (pintype "passive"))
      (node (ref "S5") (pin "1") (pinfunction "1_1") (pintype "bidirectional"))
      (node (ref "U4") (pin "17") (pinfunction "RESET_17") (pintype "input"))
    )
    (net (code "41") (name "RTS") (class "Default")
      (node (ref "IC1") (pin "19") (pinfunction "RTS_19") (pintype "output"))
      (node (ref "Q1") (pin "2") (pinfunction "E_2") (pintype "passive"))
      (node (ref "R5") (pin "1") (pinfunction "1_1") (pintype "passive"))
    )
    (net (code "42") (name "RXD") (class "Default")
      (node (ref "IC3") (pin "15") (pinfunction "RXD0_15") (pintype "bidirectional"))
      (node (ref "R11") (pin "2") (pinfunction "2_2") (pintype "passive"))
    )
    (net (code "43") (name "SCK") (class "Default")
      (node (ref "DISP1") (pin "4") (pinfunction "CLOCK_4") (pintype "input"))
      (node (ref "IC3") (pin "5") (pinfunction "GPIO14_5") (pintype "bidirectional"))
      (node (ref "U4") (pin "13") (pinfunction "SCK_13") (pintype "input"))
    )
    (net (code "44") (name "TFT_CS") (class "Default")
      (node (ref "DISP1") (pin "7") (pinfunction "CS_7") (pintype "input"))
      (node (ref "IC3") (pin "12") (pinfunction "GPIO0_12") (pintype "bidirectional"))
      (node (ref "Q2") (pin "3") (pinfunction "C_3") (pintype "passive"))
    )
    (net (code "45") (name "TFT_DC") (class "Default")
      (node (ref "DISP1") (pin "5") (pinfunction "RS/DC_5") (pintype "input"))
      (node (ref "IC3") (pin "10") (pinfunction "GPIO15_10") (pintype "bidirectional"))
      (node (ref "R6") (pin "2") (pinfunction "2_2") (pintype "passive"))
    )
    (net (code "46") (name "TXD") (class "Default")
      (node (ref "IC1") (pin "20") (pinfunction "RXD_20") (pintype "input"))
      (node (ref "IC3") (pin "16") (pinfunction "TXD0_16") (pintype "bidirectional"))
      (node (ref "Q4") (pin "2") (pinfunction "S_2") (pintype "passive"))
      (node (ref "R16") (pin "2") (pinfunction "2_2") (pintype "passive"))
    )
    (net (code "47") (name "TXD_5V") (class "Default")
      (node (ref "Q4") (pin "3") (pinfunction "D_3") (pintype "passive"))
      (node (ref "R17") (pin "2") (pinfunction "2_2") (pintype "passive"))
      (node (ref "R26") (pin "1") (pinfunction "1_1") (pintype "passive"))
    )
    (net (code "48") (name "USB_RX") (class "Default")
      (node (ref "IC1") (pin "21") (pinfunction "TXD_21") (pintype "output"))
      (node (ref "R11") (pin "1") (pinfunction "1_1") (pintype "passive"))
    )
    (net (code "49") (name "VCC") (class "Default")
      (node (ref "C6") (pin "1") (pinfunction "P$1_1") (pintype "passive"))
      (node (ref "C9") (pin "1") (pinfunction "1_1") (pintype "passive"))
      (node (ref "D1") (pin "C") (pinfunction "C_C") (pintype "passive"))
      (node (ref "IC1") (pin "8") (pinfunction "VBUS_8") (pintype "power_in"))
      (node (ref "J1") (pin "VBUS") (pinfunction "VBUS_VBUS") (pintype "bidirectional"))
      (node (ref "LED4") (pin "1-VDD") (pinfunction "VDD_1-VDD") (pintype "power_in"))
      (node (ref "R17") (pin "1") (pinfunction "1_1") (pintype "passive"))
      (node (ref "R7") (pin "2") (pinfunction "2_2") (pintype "passive"))
      (node (ref "U2") (pin "1") (pinfunction "IN_1") (pintype "bidirectional"))
    )
    (net (code "50") (name "unconnected-(IC1A-#RST-Pad9)") (class "Default")
      (node (ref "IC1") (pin "9") (pinfunction "#RST_9") (pintype "bidirectional"))
    )
    (net (code "51") (name "unconnected-(IC1A-#SUSPEND-Pad15)") (class "Default")
      (node (ref "IC1") (pin "15") (pinfunction "#SUSPEND_15") (pintype "output"))
    )
    (net (code "52") (name "unconnected-(IC1A-CTS-Pad18)") (class "Default")
      (node (ref "IC1") (pin "18") (pinfunction "CTS_18") (pintype "input"))
    )
    (net (code "53") (name "unconnected-(IC1A-DCD-Pad24)") (class "Default")
      (node (ref "IC1") (pin "24") (pinfunction "DCD_24") (pintype "input"))
    )
    (net (code "54") (name "unconnected-(IC1A-DSR-Pad22)") (class "Default")
      (node (ref "IC1") (pin "22") (pinfunction "DSR_22") (pintype "input"))
    )
    (net (code "55") (name "unconnected-(IC1A-GPIO0{slash}TXLED-Pad14)") (class "Default")
      (node (ref "IC1") (pin "14") (pinfunction "GPIO0/TXLED_14") (pintype "bidirectional"))
    )
    (net (code "56") (name "unconnected-(IC1A-GPIO1{slash}RXLED-Pad13)") (class "Default")
      (node (ref "IC1") (pin "13") (pinfunction "GPIO1/RXLED_13") (pintype "bidirectional"))
    )
    (net (code "57") (name "unconnected-(IC1A-GPIO2-Pad12)") (class "Default")
      (node (ref "IC1") (pin "12") (pinfunction "GPIO2_12") (pintype "bidirectional"))
    )
    (net (code "58") (name "unconnected-(IC1A-GPIO3-Pad11)") (class "Default")
      (node (ref "IC1") (pin "11") (pinfunction "GPIO3_11") (pintype "bidirectional"))
    )
    (net (code "59") (name "unconnected-(IC1A-NC-Pad10)") (class "Default")
      (node (ref "IC1") (pin "10") (pinfunction "NC_10") (pintype "no_connect"))
    )
    (net (code "60") (name "unconnected-(IC1A-RI-Pad1)") (class "Default")
      (node (ref "IC1") (pin "1") (pinfunction "RI_1") (pintype "input"))
    )
    (net (code "61") (name "unconnected-(IC1A-SUSPEND-Pad17)") (class "Default")
      (node (ref "IC1") (pin "17") (pinfunction "SUSPEND_17") (pintype "output"))
    )
    (net (code "62") (name "unconnected-(IC1A-VPP-Pad16)") (class "Default")
      (node (ref "IC1") (pin "16") (pinfunction "VPP_16") (pintype "bidirectional"))
    )
    (net (code "63") (name "unconnected-(IC4-PadPGOOD)") (class "Default")
      (node (ref "IC4") (pin "PGOOD") (pinfunction "PGOOD_PGOOD") (pintype "bidirectional"))
    )
    (net (code "64") (name "unconnected-(IC6-VREF-Pad5)") (class "Default")
      (node (ref "IC6") (pin "5") (pinfunction "VREF_5") (pintype "bidirectional"))
    )
    (net (code "65") (name "unconnected-(J1-PadID)") (class "Default")
      (node (ref "J1") (pin "ID") (pinfunction "ID_ID") (pintype "bidirectional"))
    )
    (net (code "66") (name "unconnected-(J5-PadMH1)") (class "Default")
      (node (ref "J5") (pin "MH1") (pinfunction "MH1_MH1") (pintype "bidirectional"))
    )
    (net (code "67") (name "unconnected-(J5-PadMH2)") (class "Default")
      (node (ref "J5") (pin "MH2") (pinfunction "MH2_MH2") (pintype "bidirectional"))
    )
    (net (code "68") (name "unconnected-(LED4-DO-Pad2-DOUT)") (class "Default")
      (node (ref "LED4") (pin "2-DOUT") (pinfunction "DO_2-DOUT") (pintype "output"))
    )
    (net (code "69") (name "unconnected-(S1-PadC)") (class "Default")
      (node (ref "S1") (pin "C") (pinfunction "C_C") (pintype "passive"))
    )
    (net (code "70") (name "unconnected-(U2-P4-Pad4)") (class "Default")
      (node (ref "U2") (pin "4") (pinfunction "P4_4") (pintype "bidirectional"))
    )
    (net (code "71") (name "unconnected-(U4A-CLKOUT-Pad3)") (class "Default")
      (node (ref "U4") (pin "3") (pinfunction "CLKOUT_3") (pintype "output"))
    )
    (net (code "72") (name "unconnected-(U4A-RX0BF-Pad11)") (class "Default")
      (node (ref "U4") (pin "11") (pinfunction "RX0BF_11") (pintype "output"))
    )
    (net (code "73") (name "unconnected-(U4A-RX1BF-Pad10)") (class "Default")
      (node (ref "U4") (pin "10") (pinfunction "RX1BF_10") (pintype "output"))
    )
    (net (code "74") (name "unconnected-(U4A-TX0RTS-Pad4)") (class "Default")
      (node (ref "U4") (pin "4") (pinfunction "TX0RTS_4") (pintype "input"))
    )
    (net (code "75") (name "unconnected-(U4A-TX1RTS-Pad5)") (class "Default")
      (node (ref "U4") (pin "5") (pinfunction "TX1RTS_5") (pintype "input"))
    )
    (net (code "76") (name "unconnected-(U4A-TX2RTS-Pad6)") (class "Default")
      (node (ref "U4") (pin "6") (pinfunction "TX2RTS_6") (pintype "input"))
    )
  )
)
